# IRSensor.net
KiCad netlist of a schematic drawn in EAGLE
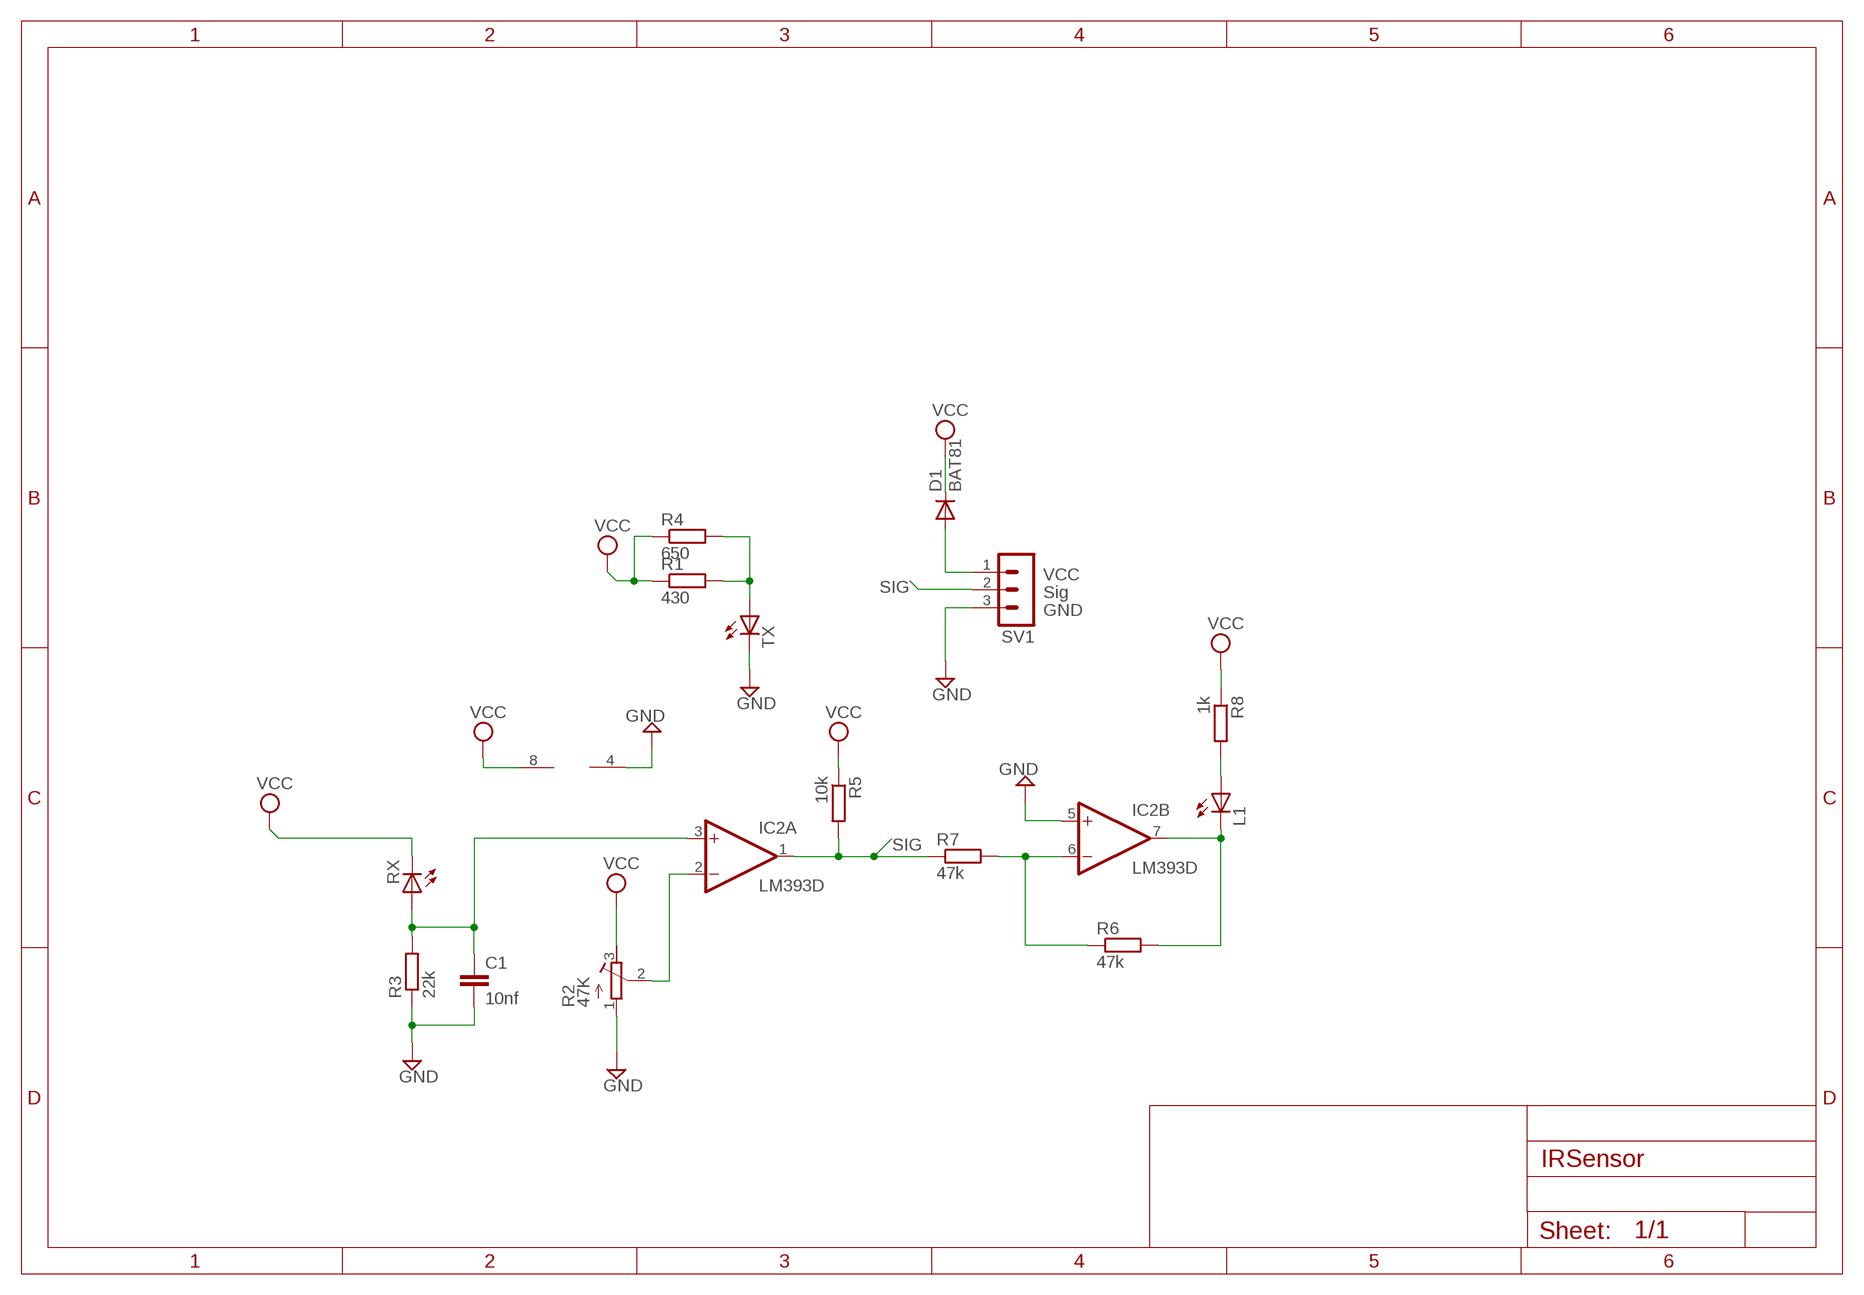
[diagram p0: schematic, sheet 1]

(export (version "E")
  (design (tool "Eeschema 10.0.6"))
  (components
    (comp (ref "C1")
      (value "10nf")
      (footprint "eagle-import:C1206")
      (libsource (lib "eagle-import") (part "C-EUC1206"))
    )
    (comp (ref "D1")
      (value "BAT81")
      (footprint "eagle-import:DO34-7")
      (libsource (lib "eagle-import") (part "BAT81"))
    )
    (comp (ref "IC2")
      (value "LM393D")
      (footprint "eagle-import:SO08")
      (libsource (lib "eagle-import") (part "LM393D"))
    )
    (comp (ref "L1")
      (value "LEDCHIPLED_0805")
      (footprint "eagle-import:CHIPLED_0805")
      (libsource (lib "eagle-import") (part "LEDCHIPLED_0805"))
    )
    (comp (ref "R1")
      (value "430")
      (footprint "eagle-import:0204_7")
      (libsource (lib "eagle-import") (part "R-EU_0204/7"))
    )
    (comp (ref "R2")
      (value "47K")
      (footprint "eagle-import:RTRIM64W")
      (libsource (lib "eagle-import") (part "R-TRIMM64W"))
    )
    (comp (ref "R3")
      (value "22k")
      (footprint "eagle-import:M1206")
      (libsource (lib "eagle-import") (part "R-EU_M1206"))
    )
    (comp (ref "R4")
      (value "650")
      (footprint "eagle-import:0204_7")
      (libsource (lib "eagle-import") (part "R-EU_0204/7"))
    )
    (comp (ref "R5")
      (value "10k")
      (footprint "eagle-import:M1206")
      (libsource (lib "eagle-import") (part "R-EU_M1206"))
    )
    (comp (ref "R6")
      (value "47k")
      (footprint "eagle-import:M1206")
      (libsource (lib "eagle-import") (part "R-EU_M1206"))
    )
    (comp (ref "R7")
      (value "47k")
      (footprint "eagle-import:M1206")
      (libsource (lib "eagle-import") (part "R-EU_M1206"))
    )
    (comp (ref "R8")
      (value "1k")
      (footprint "eagle-import:M1206")
      (libsource (lib "eagle-import") (part "R-EU_M1206"))
    )
    (comp (ref "RX")
      (value "LED3MM")
      (footprint "eagle-import:LED3MM")
      (libsource (lib "eagle-import") (part "LED3MM"))
    )
    (comp (ref "SV1")
      (value "MA03-1")
      (footprint "eagle-import:MA03-1")
      (libsource (lib "eagle-import") (part "MA03-1"))
    )
    (comp (ref "TX")
      (value "LED3MM")
      (footprint "eagle-import:LED3MM")
      (libsource (lib "eagle-import") (part "LED3MM"))
    )
  )
  (nets
    (net (code "1") (name "/SIG") (class "Default")
      (node (ref "IC2") (pin "1") (pinfunction "OUT_1") (pintype "output"))
      (node (ref "R5") (pin "2") (pinfunction "2_2") (pintype "passive"))
      (node (ref "R7") (pin "1") (pinfunction "1_1") (pintype "passive"))
      (node (ref "SV1") (pin "2") (pinfunction "2_2") (pintype "passive"))
    )
    (net (code "2") (name "GND") (class "Default")
      (node (ref "C1") (pin "2") (pinfunction "2_2") (pintype "passive"))
      (node (ref "IC2") (pin "4") (pinfunction "V-_4") (pintype "power_in"))
      (node (ref "IC2") (pin "5") (pinfunction "+IN_5") (pintype "input"))
      (node (ref "R2") (pin "1") (pinfunction "E_1") (pintype "passive"))
      (node (ref "R3") (pin "1") (pinfunction "1_1") (pintype "passive"))
      (node (ref "SV1") (pin "3") (pinfunction "3_3") (pintype "passive"))
      (node (ref "TX") (pin "K") (pinfunction "C_K") (pintype "passive"))
    )
    (net (code "3") (name "Net-(D1-PadA)") (class "Default")
      (node (ref "D1") (pin "A") (pinfunction "A_A") (pintype "passive"))
      (node (ref "SV1") (pin "1") (pinfunction "1_1") (pintype "passive"))
    )
    (net (code "4") (name "Net-(IC2A-+IN)") (class "Default")
      (node (ref "C1") (pin "1") (pinfunction "1_1") (pintype "passive"))
      (node (ref "IC2") (pin "3") (pinfunction "+IN_3") (pintype "input"))
      (node (ref "R3") (pin "2") (pinfunction "2_2") (pintype "passive"))
      (node (ref "RX") (pin "A") (pinfunction "A_A") (pintype "passive"))
    )
    (net (code "5") (name "Net-(IC2A--IN)") (class "Default")
      (node (ref "IC2") (pin "2") (pinfunction "-IN_2") (pintype "input"))
      (node (ref "R2") (pin "2") (pinfunction "S_2") (pintype "passive"))
    )
    (net (code "6") (name "Net-(IC2B--IN)") (class "Default")
      (node (ref "IC2") (pin "6") (pinfunction "-IN_6") (pintype "input"))
      (node (ref "R6") (pin "1") (pinfunction "1_1") (pintype "passive"))
      (node (ref "R7") (pin "2") (pinfunction "2_2") (pintype "passive"))
    )
    (net (code "7") (name "Net-(IC2B-OUT)") (class "Default")
      (node (ref "IC2") (pin "7") (pinfunction "OUT_7") (pintype "output"))
      (node (ref "L1") (pin "C") (pinfunction "C_C") (pintype "passive"))
      (node (ref "R6") (pin "2") (pinfunction "2_2") (pintype "passive"))
    )
    (net (code "8") (name "Net-(L1-PadA)") (class "Default")
      (node (ref "L1") (pin "A") (pinfunction "A_A") (pintype "passive"))
      (node (ref "R8") (pin "2") (pinfunction "2_2") (pintype "passive"))
    )
    (net (code "9") (name "Net-(R1-Pad2)") (class "Default")
      (node (ref "R1") (pin "2") (pinfunction "2_2") (pintype "passive"))
      (node (ref "R4") (pin "2") (pinfunction "2_2") (pintype "passive"))
      (node (ref "TX") (pin "A") (pinfunction "A_A") (pintype "passive"))
    )
    (net (code "10") (name "VCC") (class "Default")
      (node (ref "D1") (pin "C") (pinfunction "C_C") (pintype "passive"))
      (node (ref "IC2") (pin "8") (pinfunction "V+_8") (pintype "power_in"))
      (node (ref "R1") (pin "1") (pinfunction "1_1") (pintype "passive"))
      (node (ref "R2") (pin "3") (pinfunction "A_3") (pintype "passive"))
      (node (ref "R4") (pin "1") (pinfunction "1_1") (pintype "passive"))
      (node (ref "R5") (pin "1") (pinfunction "1_1") (pintype "passive"))
      (node (ref "R8") (pin "1") (pinfunction "1_1") (pintype "passive"))
      (node (ref "RX") (pin "K") (pinfunction "C_K") (pintype "passive"))
    )
  )
)
